# Power.net
KiCad netlist of a schematic drawn in Altium Designer
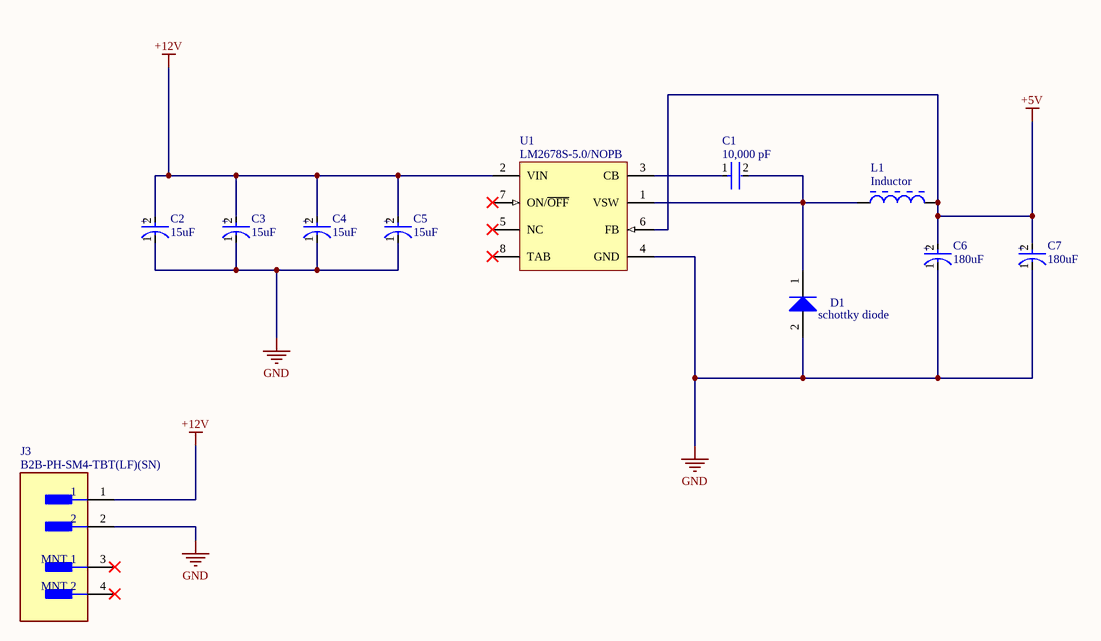
[diagram p0: Power.SchDoc]

(export (version "E")
  (design (tool "Eeschema 10.0.6"))
  (components
    (comp (ref "C1")
      (value "10,000 pF")
      (footprint "FP-C0805C-DN-MFG")
      (description "CAP CER 10000PF 100V X7R 0805")
      (fields
        (field (name "OCTOPART") "https://octopart.com/c0805c103k1ractu-kemet-97824")
        (field (name "MANUFACTURER") "KEMET")
      )
      (libsource (lib "Altium Content Vault") (part "b4654b650e69147ec39a6b967a45e02"))
    )
    (comp (ref "C2")
      (value "TAJS156K006RNJ")
      (footprint "FP-TAJS-MFG")
      (description "15uF 6.3V  ±10% 3.5Ω 1206  SMD Tantalum Capacitor")
      (fields
        (field (name "CAPACITANCE") "15uF")
        (field (name "TOLERANCE") "10%")
        (field (name "VOLTAGE") "6.3V")
      )
      (libsource (lib "Altium Content Vault") (part "a00bbbee19879c290e62620ae7e47b1"))
    )
    (comp (ref "C3")
      (value "TAJS156K006RNJ")
      (footprint "FP-TAJS-MFG")
      (description "15uF 6.3V  ±10% 3.5Ω 1206  SMD Tantalum Capacitor")
      (fields
        (field (name "CAPACITANCE") "15uF")
        (field (name "TOLERANCE") "10%")
        (field (name "VOLTAGE") "6.3V")
      )
      (libsource (lib "Altium Content Vault") (part "a00bbbee19879c290e62620ae7e47b1"))
    )
    (comp (ref "C4")
      (value "TAJS156K006RNJ")
      (footprint "FP-TAJS-MFG")
      (description "15uF 6.3V  ±10% 3.5Ω 1206  SMD Tantalum Capacitor")
      (fields
        (field (name "CAPACITANCE") "15uF")
        (field (name "TOLERANCE") "10%")
        (field (name "VOLTAGE") "6.3V")
      )
      (libsource (lib "Altium Content Vault") (part "a00bbbee19879c290e62620ae7e47b1"))
    )
    (comp (ref "C5")
      (value "TAJS156K006RNJ")
      (footprint "FP-TAJS-MFG")
      (description "15uF 6.3V  ±10% 3.5Ω 1206  SMD Tantalum Capacitor")
      (fields
        (field (name "CAPACITANCE") "15uF")
        (field (name "TOLERANCE") "10%")
        (field (name "VOLTAGE") "6.3V")
      )
      (libsource (lib "Altium Content Vault") (part "a00bbbee19879c290e62620ae7e47b1"))
    )
    (comp (ref "C6")
      (value "EEFSX0D181ER")
      (footprint "FP-SP-Cap-X-MFG")
      (description "Molded Aluminum Polymer Capacitor 180uF 20% 2V life 2000Hours SMD 2917")
      (fields
        (field (name "VOLTAGE") "2V")
        (field (name "CAPACITANCE") "180uF")
        (field (name "TOLERANCE") "20%")
      )
      (libsource (lib "Altium Content Vault") (part "203bc49f2ac43e59fd269a8c329ed05"))
    )
    (comp (ref "C7")
      (value "EEFSX0D181ER")
      (footprint "FP-SP-Cap-X-MFG")
      (description "Molded Aluminum Polymer Capacitor 180uF 20% 2V life 2000Hours SMD 2917")
      (fields
        (field (name "VOLTAGE") "2V")
        (field (name "CAPACITANCE") "180uF")
        (field (name "TOLERANCE") "20%")
      )
      (libsource (lib "Altium Content Vault") (part "203bc49f2ac43e59fd269a8c329ed05"))
    )
    (comp (ref "D1")
      (value "BAS3010B-03W")
      (footprint "INF-SOD323_V")
      (description "Medium Power AF Schottky Diode, -65 to 125 degC, SOD323, Reel, Green")
      (fields (field (name "MANUFACTURER") "Infineon") (field (name "MODEL") "schottky diode"))
      (libsource (lib "Altium Content Vault") (part "INF-D_K1A2-2"))
    )
    (comp (ref "J3")
      (value "B2B-PH-SM4-TBT(LF)(SN)")
      (footprint "FP-B2B-PH-SM4-TBT_LF_SN-MFG")
      (description "CONN HEADER SMD 2POS 2MM")
      (fields
        (field (name "OCTOPART") "https://octopart.com/b2b-ph-sm4-tbt%28lf%29%28sn%29-jst-7877930")
        (field (name "MANUFACTURER") "JST")
      )
      (libsource (lib "Altium Content Vault") (part "56ec3178a87b3978bdc1b3682cd516a"))
    )
    (comp (ref "L1")
      (value "SRN3015-220M")
      (footprint "BOUR-SRN3015-2_V")
      (fields (field (name "MANUFACTURER") "Bourns") (field (name "MODEL") "Inductor"))
      (libsource (lib "Altium Content Vault") (part "BOUR-IND-2A"))
    )
    (comp (ref "U1")
      (value "LM2678S-5.0/NOPB")
      (footprint "KTW0007B_L")
      (description "SIMPLE SWITCHER® High Efficiency 5A Step-Down Voltage Regulator, 7-pin TO-263, Pb-Free")
      (fields (field (name "MANUFACTURER") "Texas Instruments"))
      (libsource (lib "Altium Content Vault") (part "PM-REG-LM2678S"))
    )
  )
  (nets
    (net (code "1") (name "+5V") (class "Default")
      (node (ref "C6") (pin "2") (pinfunction "A_2") (pintype "passive"))
      (node (ref "C7") (pin "2") (pinfunction "A_2") (pintype "passive"))
      (node (ref "L1") (pin "2") (pinfunction "2_2") (pintype "passive"))
      (node (ref "U1") (pin "6") (pinfunction "FB_6") (pintype "input"))
    )
    (net (code "2") (name "+12V") (class "Default")
      (node (ref "C2") (pin "2") (pinfunction "A_2") (pintype "passive"))
      (node (ref "C3") (pin "2") (pinfunction "A_2") (pintype "passive"))
      (node (ref "C4") (pin "2") (pinfunction "A_2") (pintype "passive"))
      (node (ref "C5") (pin "2") (pinfunction "A_2") (pintype "passive"))
      (node (ref "J3") (pin "1") (pinfunction "1_1") (pintype "passive"))
      (node (ref "U1") (pin "2") (pinfunction "VIN_2") (pintype "power_in"))
    )
    (net (code "3") (name "GND") (class "Default")
      (node (ref "C2") (pin "1") (pinfunction "C_1") (pintype "passive"))
      (node (ref "C3") (pin "1") (pinfunction "C_1") (pintype "passive"))
      (node (ref "C4") (pin "1") (pinfunction "C_1") (pintype "passive"))
      (node (ref "C5") (pin "1") (pinfunction "C_1") (pintype "passive"))
      (node (ref "C6") (pin "1") (pinfunction "C_1") (pintype "passive"))
      (node (ref "C7") (pin "1") (pinfunction "C_1") (pintype "passive"))
      (node (ref "D1") (pin "2") (pinfunction "A_2") (pintype "passive"))
      (node (ref "J3") (pin "2") (pinfunction "2_2") (pintype "passive"))
      (node (ref "U1") (pin "4") (pinfunction "GND_4") (pintype "power_in"))
    )
    (net (code "4") (name "Net-(D1-K)") (class "Default")
      (node (ref "C1") (pin "2") (pinfunction "2_2") (pintype "passive"))
      (node (ref "D1") (pin "1") (pinfunction "K_1") (pintype "passive"))
      (node (ref "L1") (pin "1") (pinfunction "1_1") (pintype "passive"))
      (node (ref "U1") (pin "1") (pinfunction "VSW_1") (pintype "power_in"))
    )
    (net (code "5") (name "Net-(U1-CB)") (class "Default")
      (node (ref "C1") (pin "1") (pinfunction "1_1") (pintype "passive"))
      (node (ref "U1") (pin "3") (pinfunction "CB_3") (pintype "passive"))
    )
    (net (code "6") (name "unconnected-(J3-MNT_1-Pad3)") (class "Default")
      (node (ref "J3") (pin "3") (pinfunction "MNT_1_3") (pintype "passive+no_connect"))
    )
    (net (code "7") (name "unconnected-(J3-MNT_2-Pad4)") (class "Default")
      (node (ref "J3") (pin "4") (pinfunction "MNT_2_4") (pintype "passive+no_connect"))
    )
    (net (code "8") (name "unconnected-(U1-NC-Pad5)") (class "Default")
      (node (ref "U1") (pin "5") (pinfunction "NC_5") (pintype "passive+no_connect"))
    )
    (net (code "9") (name "unconnected-(U1-ON{slash}~{OFF}-Pad7)") (class "Default")
      (node (ref "U1") (pin "7") (pinfunction "ON/~{OFF}_7") (pintype "input+no_connect"))
    )
    (net (code "10") (name "unconnected-(U1-TAB-Pad8)") (class "Default")
      (node (ref "U1") (pin "8") (pinfunction "TAB_8") (pintype "power_in+no_connect"))
    )
  )
)
